# ADC.net
KiCad netlist of a schematic drawn in EAGLE
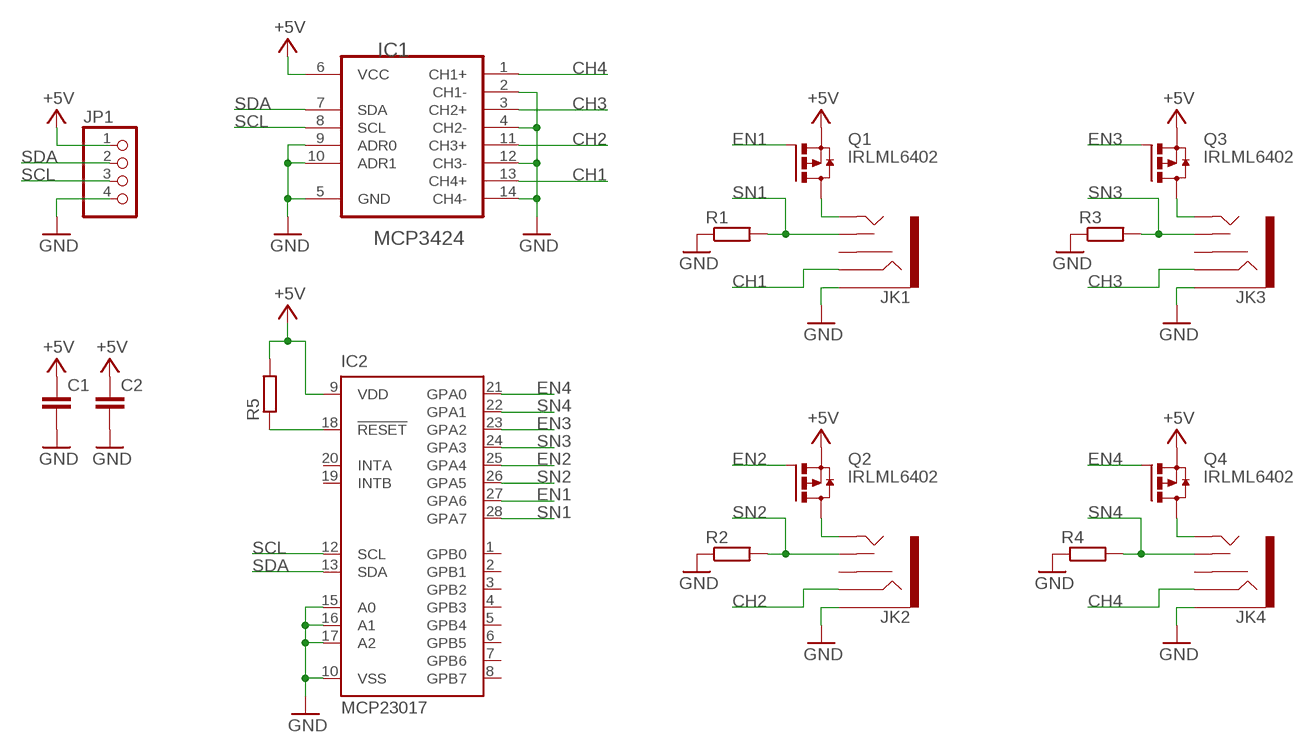
[diagram p0: schematic, sheet 1]

(export (version "E")
  (design (tool "Eeschema 10.0.6"))
  (components
    (comp (ref "C1")
      (value "C-EUC0805K")
      (footprint "eagle-import:C0805K")
      (libsource (lib "eagle-import") (part "C-EUC0805K"))
    )
    (comp (ref "C2")
      (value "C-EUC0805K")
      (footprint "eagle-import:C0805K")
      (libsource (lib "eagle-import") (part "C-EUC0805K"))
    )
    (comp (ref "IC1")
      (value "MCP3424")
      (footprint "eagle-import:SO14")
      (fields (field (name "MPN") "MCP3424-E/SL"))
      (libsource (lib "eagle-import") (part "MCP3424"))
    )
    (comp (ref "IC2")
      (value "MCP23017")
      (footprint "eagle-import:SO28W")
      (fields (field (name "MF") "MICROCHIP") (field (name "MPN") "MCP23017-E/SO"))
      (libsource (lib "eagle-import") (part "MCP23017SO"))
    )
    (comp (ref "JK1")
      (value "AUDIO-JACK2PTH")
      (footprint "eagle-import:AUDIO-JACK")
      (libsource (lib "eagle-import") (part "AUDIO-JACK2PTH"))
    )
    (comp (ref "JK2")
      (value "AUDIO-JACK2PTH")
      (footprint "eagle-import:AUDIO-JACK")
      (libsource (lib "eagle-import") (part "AUDIO-JACK2PTH"))
    )
    (comp (ref "JK3")
      (value "AUDIO-JACK2PTH")
      (footprint "eagle-import:AUDIO-JACK")
      (libsource (lib "eagle-import") (part "AUDIO-JACK2PTH"))
    )
    (comp (ref "JK4")
      (value "AUDIO-JACK2PTH")
      (footprint "eagle-import:AUDIO-JACK")
      (libsource (lib "eagle-import") (part "AUDIO-JACK2PTH"))
    )
    (comp (ref "JP1")
      (value "PINHD-1X4")
      (footprint "eagle-import:1X04")
      (libsource (lib "eagle-import") (part "PINHD-1X4"))
    )
    (comp (ref "Q1")
      (value "IRLML6402")
      (footprint "eagle-import:SOT23")
      (libsource (lib "eagle-import") (part "IRLML6402"))
    )
    (comp (ref "Q2")
      (value "IRLML6402")
      (footprint "eagle-import:SOT23")
      (libsource (lib "eagle-import") (part "IRLML6402"))
    )
    (comp (ref "Q3")
      (value "IRLML6402")
      (footprint "eagle-import:SOT23")
      (libsource (lib "eagle-import") (part "IRLML6402"))
    )
    (comp (ref "Q4")
      (value "IRLML6402")
      (footprint "eagle-import:SOT23")
      (libsource (lib "eagle-import") (part "IRLML6402"))
    )
    (comp (ref "R1")
      (value "R-EU_R0805")
      (footprint "eagle-import:R0805")
      (libsource (lib "eagle-import") (part "R-EU_R0805"))
    )
    (comp (ref "R2")
      (value "R-EU_R0805")
      (footprint "eagle-import:R0805")
      (libsource (lib "eagle-import") (part "R-EU_R0805"))
    )
    (comp (ref "R3")
      (value "R-EU_R0805")
      (footprint "eagle-import:R0805")
      (libsource (lib "eagle-import") (part "R-EU_R0805"))
    )
    (comp (ref "R4")
      (value "R-EU_R0805")
      (footprint "eagle-import:R0805")
      (libsource (lib "eagle-import") (part "R-EU_R0805"))
    )
    (comp (ref "R5")
      (value "R-EU_R0805")
      (footprint "eagle-import:R0805")
      (libsource (lib "eagle-import") (part "R-EU_R0805"))
    )
  )
  (nets
    (net (code "1") (name "+5V") (class "Default")
      (node (ref "C1") (pin "1") (pinfunction "1_1") (pintype "passive"))
      (node (ref "C2") (pin "1") (pinfunction "1_1") (pintype "passive"))
      (node (ref "IC1") (pin "6") (pinfunction "VCC_6") (pintype "power_in"))
      (node (ref "IC2") (pin "9") (pinfunction "VDD_9") (pintype "power_in"))
      (node (ref "JP1") (pin "1") (pinfunction "1_1") (pintype "passive"))
      (node (ref "Q1") (pin "2") (pinfunction "S_2") (pintype "passive"))
      (node (ref "Q2") (pin "2") (pinfunction "S_2") (pintype "passive"))
      (node (ref "Q3") (pin "2") (pinfunction "S_2") (pintype "passive"))
      (node (ref "Q4") (pin "2") (pinfunction "S_2") (pintype "passive"))
      (node (ref "R5") (pin "2") (pinfunction "2_2") (pintype "passive"))
    )
    (net (code "2") (name "/CH1") (class "Default")
      (node (ref "IC1") (pin "13") (pinfunction "CH4+_13") (pintype "input"))
      (node (ref "JK1") (pin "RING") (pinfunction "RING_RING") (pintype "bidirectional"))
    )
    (net (code "3") (name "/CH2") (class "Default")
      (node (ref "IC1") (pin "11") (pinfunction "CH3+_11") (pintype "input"))
      (node (ref "JK2") (pin "RING") (pinfunction "RING_RING") (pintype "bidirectional"))
    )
    (net (code "4") (name "/CH3") (class "Default")
      (node (ref "IC1") (pin "3") (pinfunction "CH2+_3") (pintype "input"))
      (node (ref "JK3") (pin "RING") (pinfunction "RING_RING") (pintype "bidirectional"))
    )
    (net (code "5") (name "/CH4") (class "Default")
      (node (ref "IC1") (pin "1") (pinfunction "CH1+_1") (pintype "input"))
      (node (ref "JK4") (pin "RING") (pinfunction "RING_RING") (pintype "bidirectional"))
    )
    (net (code "6") (name "/EN1") (class "Default")
      (node (ref "IC2") (pin "27") (pinfunction "GPA6_27") (pintype "bidirectional"))
      (node (ref "Q1") (pin "1") (pinfunction "G_1") (pintype "passive"))
    )
    (net (code "7") (name "/EN2") (class "Default")
      (node (ref "IC2") (pin "25") (pinfunction "GPA4_25") (pintype "bidirectional"))
      (node (ref "Q2") (pin "1") (pinfunction "G_1") (pintype "passive"))
    )
    (net (code "8") (name "/EN3") (class "Default")
      (node (ref "IC2") (pin "23") (pinfunction "GPA2_23") (pintype "bidirectional"))
      (node (ref "Q3") (pin "1") (pinfunction "G_1") (pintype "passive"))
    )
    (net (code "9") (name "/EN4") (class "Default")
      (node (ref "IC2") (pin "21") (pinfunction "GPA0_21") (pintype "bidirectional"))
      (node (ref "Q4") (pin "1") (pinfunction "G_1") (pintype "passive"))
    )
    (net (code "10") (name "/SCL") (class "Default")
      (node (ref "IC1") (pin "8") (pinfunction "SCL_8") (pintype "input"))
      (node (ref "IC2") (pin "12") (pinfunction "SCL_12") (pintype "input"))
      (node (ref "JP1") (pin "3") (pinfunction "3_3") (pintype "passive"))
    )
    (net (code "11") (name "/SDA") (class "Default")
      (node (ref "IC1") (pin "7") (pinfunction "SDA_7") (pintype "bidirectional"))
      (node (ref "IC2") (pin "13") (pinfunction "SDA_13") (pintype "bidirectional"))
      (node (ref "JP1") (pin "2") (pinfunction "2_2") (pintype "passive"))
    )
    (net (code "12") (name "/SN1") (class "Default")
      (node (ref "IC2") (pin "28") (pinfunction "GPA7_28") (pintype "bidirectional"))
      (node (ref "JK1") (pin "TSH") (pinfunction "TSH_TSH") (pintype "bidirectional"))
      (node (ref "R1") (pin "2") (pinfunction "2_2") (pintype "passive"))
    )
    (net (code "13") (name "/SN2") (class "Default")
      (node (ref "IC2") (pin "26") (pinfunction "GPA5_26") (pintype "bidirectional"))
      (node (ref "JK2") (pin "TSH") (pinfunction "TSH_TSH") (pintype "bidirectional"))
      (node (ref "R2") (pin "2") (pinfunction "2_2") (pintype "passive"))
    )
    (net (code "14") (name "/SN3") (class "Default")
      (node (ref "IC2") (pin "24") (pinfunction "GPA3_24") (pintype "bidirectional"))
      (node (ref "JK3") (pin "TSH") (pinfunction "TSH_TSH") (pintype "bidirectional"))
      (node (ref "R3") (pin "2") (pinfunction "2_2") (pintype "passive"))
    )
    (net (code "15") (name "/SN4") (class "Default")
      (node (ref "IC2") (pin "22") (pinfunction "GPA1_22") (pintype "bidirectional"))
      (node (ref "JK4") (pin "TSH") (pinfunction "TSH_TSH") (pintype "bidirectional"))
      (node (ref "R4") (pin "2") (pinfunction "2_2") (pintype "passive"))
    )
    (net (code "16") (name "GND") (class "Default")
      (node (ref "C1") (pin "2") (pinfunction "2_2") (pintype "passive"))
      (node (ref "C2") (pin "2") (pinfunction "2_2") (pintype "passive"))
      (node (ref "IC1") (pin "10") (pinfunction "ADR1_10") (pintype "input"))
      (node (ref "IC1") (pin "12") (pinfunction "CH3-_12") (pintype "input"))
      (node (ref "IC1") (pin "14") (pinfunction "CH4-_14") (pintype "input"))
      (node (ref "IC1") (pin "2") (pinfunction "CH1-_2") (pintype "input"))
      (node (ref "IC1") (pin "4") (pinfunction "CH2-_4") (pintype "input"))
      (node (ref "IC1") (pin "5") (pinfunction "GND_5") (pintype "power_in"))
      (node (ref "IC1") (pin "9") (pinfunction "ADR0_9") (pintype "input"))
      (node (ref "IC2") (pin "10") (pinfunction "VSS_10") (pintype "power_in"))
      (node (ref "IC2") (pin "15") (pinfunction "A0_15") (pintype "input"))
      (node (ref "IC2") (pin "16") (pinfunction "A1_16") (pintype "input"))
      (node (ref "IC2") (pin "17") (pinfunction "A2_17") (pintype "input"))
      (node (ref "JK1") (pin "SLEEVE") (pinfunction "SLEEVE_SLEEVE") (pintype "bidirectional"))
      (node (ref "JK2") (pin "SLEEVE") (pinfunction "SLEEVE_SLEEVE") (pintype "bidirectional"))
      (node (ref "JK3") (pin "SLEEVE") (pinfunction "SLEEVE_SLEEVE") (pintype "bidirectional"))
      (node (ref "JK4") (pin "SLEEVE") (pinfunction "SLEEVE_SLEEVE") (pintype "bidirectional"))
      (node (ref "JP1") (pin "4") (pinfunction "4_4") (pintype "passive"))
      (node (ref "R1") (pin "1") (pinfunction "1_1") (pintype "passive"))
      (node (ref "R2") (pin "1") (pinfunction "1_1") (pintype "passive"))
      (node (ref "R3") (pin "1") (pinfunction "1_1") (pintype "passive"))
      (node (ref "R4") (pin "1") (pinfunction "1_1") (pintype "passive"))
    )
    (net (code "17") (name "Net-(IC2-~{RESET})") (class "Default")
      (node (ref "IC2") (pin "18") (pinfunction "~{RESET}_18") (pintype "input"))
      (node (ref "R5") (pin "1") (pinfunction "1_1") (pintype "passive"))
    )
    (net (code "18") (name "Net-(Q1-D)") (class "Default")
      (node (ref "JK1") (pin "TIP") (pinfunction "TIP_TIP") (pintype "bidirectional"))
      (node (ref "Q1") (pin "3") (pinfunction "D_3") (pintype "passive"))
    )
    (net (code "19") (name "Net-(Q2-D)") (class "Default")
      (node (ref "JK2") (pin "TIP") (pinfunction "TIP_TIP") (pintype "bidirectional"))
      (node (ref "Q2") (pin "3") (pinfunction "D_3") (pintype "passive"))
    )
    (net (code "20") (name "Net-(Q3-D)") (class "Default")
      (node (ref "JK3") (pin "TIP") (pinfunction "TIP_TIP") (pintype "bidirectional"))
      (node (ref "Q3") (pin "3") (pinfunction "D_3") (pintype "passive"))
    )
    (net (code "21") (name "Net-(Q4-D)") (class "Default")
      (node (ref "JK4") (pin "TIP") (pinfunction "TIP_TIP") (pintype "bidirectional"))
      (node (ref "Q4") (pin "3") (pinfunction "D_3") (pintype "passive"))
    )
    (net (code "22") (name "unconnected-(IC2-GPB0-Pad1)") (class "Default")
      (node (ref "IC2") (pin "1") (pinfunction "GPB0_1") (pintype "bidirectional"))
    )
    (net (code "23") (name "unconnected-(IC2-GPB1-Pad2)") (class "Default")
      (node (ref "IC2") (pin "2") (pinfunction "GPB1_2") (pintype "bidirectional"))
    )
    (net (code "24") (name "unconnected-(IC2-GPB2-Pad3)") (class "Default")
      (node (ref "IC2") (pin "3") (pinfunction "GPB2_3") (pintype "bidirectional"))
    )
    (net (code "25") (name "unconnected-(IC2-GPB3-Pad4)") (class "Default")
      (node (ref "IC2") (pin "4") (pinfunction "GPB3_4") (pintype "bidirectional"))
    )
    (net (code "26") (name "unconnected-(IC2-GPB4-Pad5)") (class "Default")
      (node (ref "IC2") (pin "5") (pinfunction "GPB4_5") (pintype "bidirectional"))
    )
    (net (code "27") (name "unconnected-(IC2-GPB5-Pad6)") (class "Default")
      (node (ref "IC2") (pin "6") (pinfunction "GPB5_6") (pintype "bidirectional"))
    )
    (net (code "28") (name "unconnected-(IC2-GPB6-Pad7)") (class "Default")
      (node (ref "IC2") (pin "7") (pinfunction "GPB6_7") (pintype "bidirectional"))
    )
    (net (code "29") (name "unconnected-(IC2-GPB7-Pad8)") (class "Default")
      (node (ref "IC2") (pin "8") (pinfunction "GPB7_8") (pintype "bidirectional"))
    )
    (net (code "30") (name "unconnected-(IC2-INTA-Pad20)") (class "Default")
      (node (ref "IC2") (pin "20") (pinfunction "INTA_20") (pintype "output"))
    )
    (net (code "31") (name "unconnected-(IC2-INTB-Pad19)") (class "Default")
      (node (ref "IC2") (pin "19") (pinfunction "INTB_19") (pintype "output"))
    )
    (net (code "32") (name "unconnected-(JK1-PadRSH)") (class "Default")
      (node (ref "JK1") (pin "RSH") (pinfunction "RSH_RSH") (pintype "bidirectional"))
    )
    (net (code "33") (name "unconnected-(JK2-PadRSH)") (class "Default")
      (node (ref "JK2") (pin "RSH") (pinfunction "RSH_RSH") (pintype "bidirectional"))
    )
    (net (code "34") (name "unconnected-(JK3-PadRSH)") (class "Default")
      (node (ref "JK3") (pin "RSH") (pinfunction "RSH_RSH") (pintype "bidirectional"))
    )
    (net (code "35") (name "unconnected-(JK4-PadRSH)") (class "Default")
      (node (ref "JK4") (pin "RSH") (pinfunction "RSH_RSH") (pintype "bidirectional"))
    )
  )
)
